# full_schema.net
KiCad netlist of a schematic drawn in EAGLE
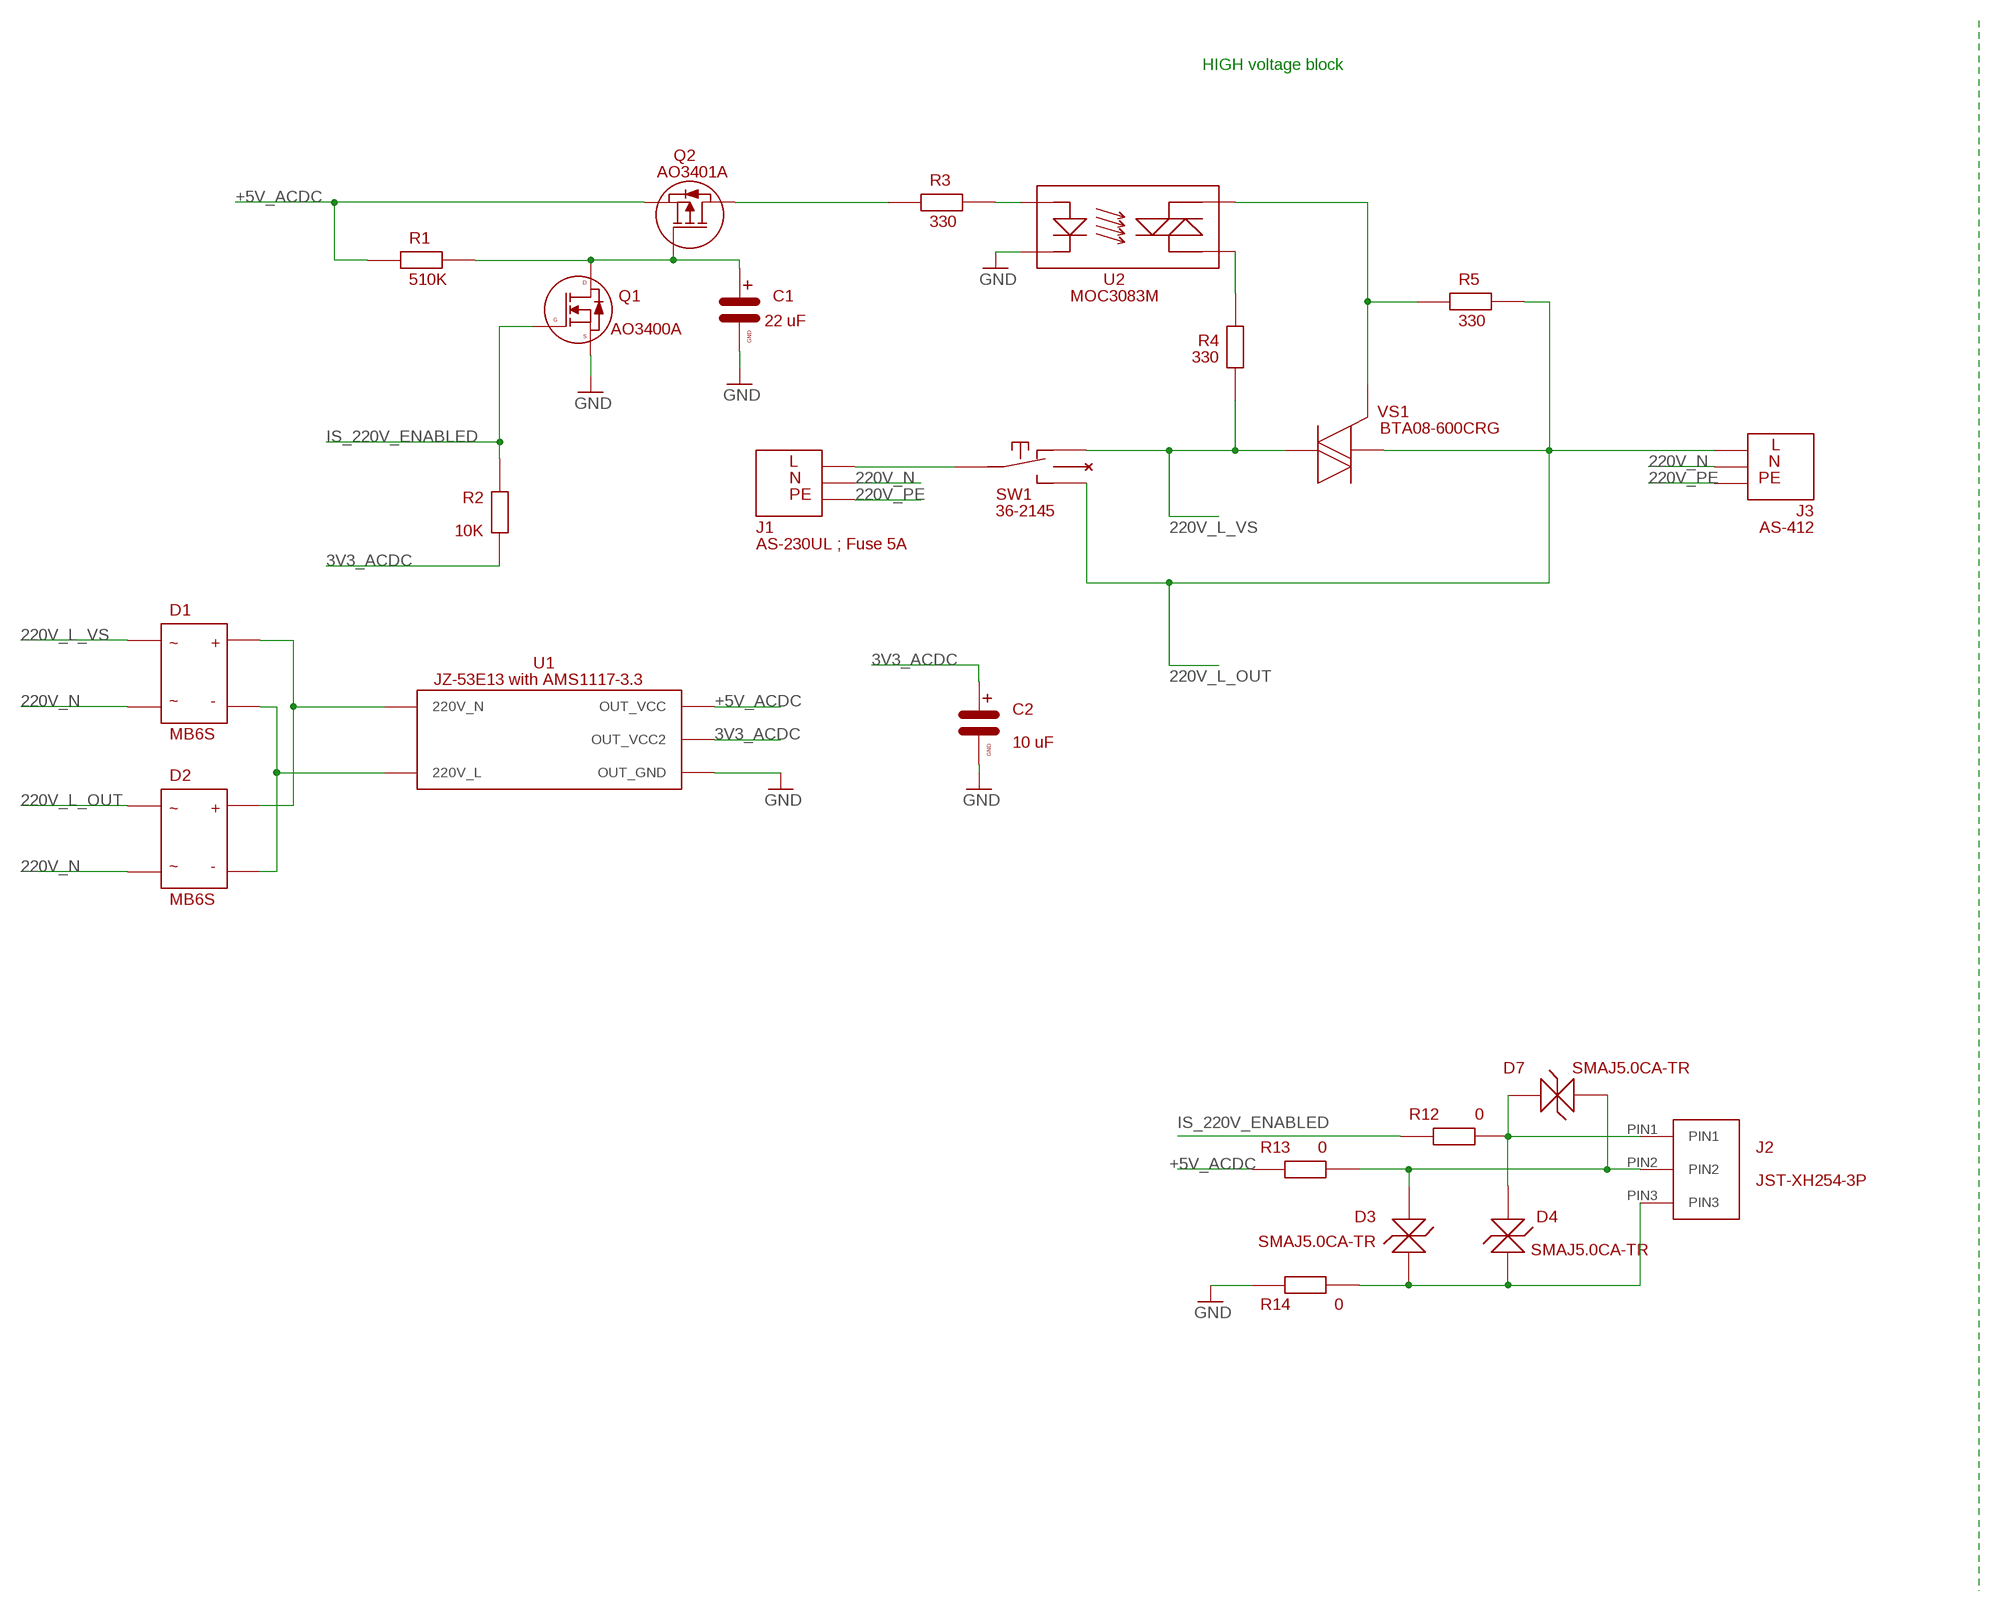
[diagram p0: schematic, sheet 1, part 1 of 2]
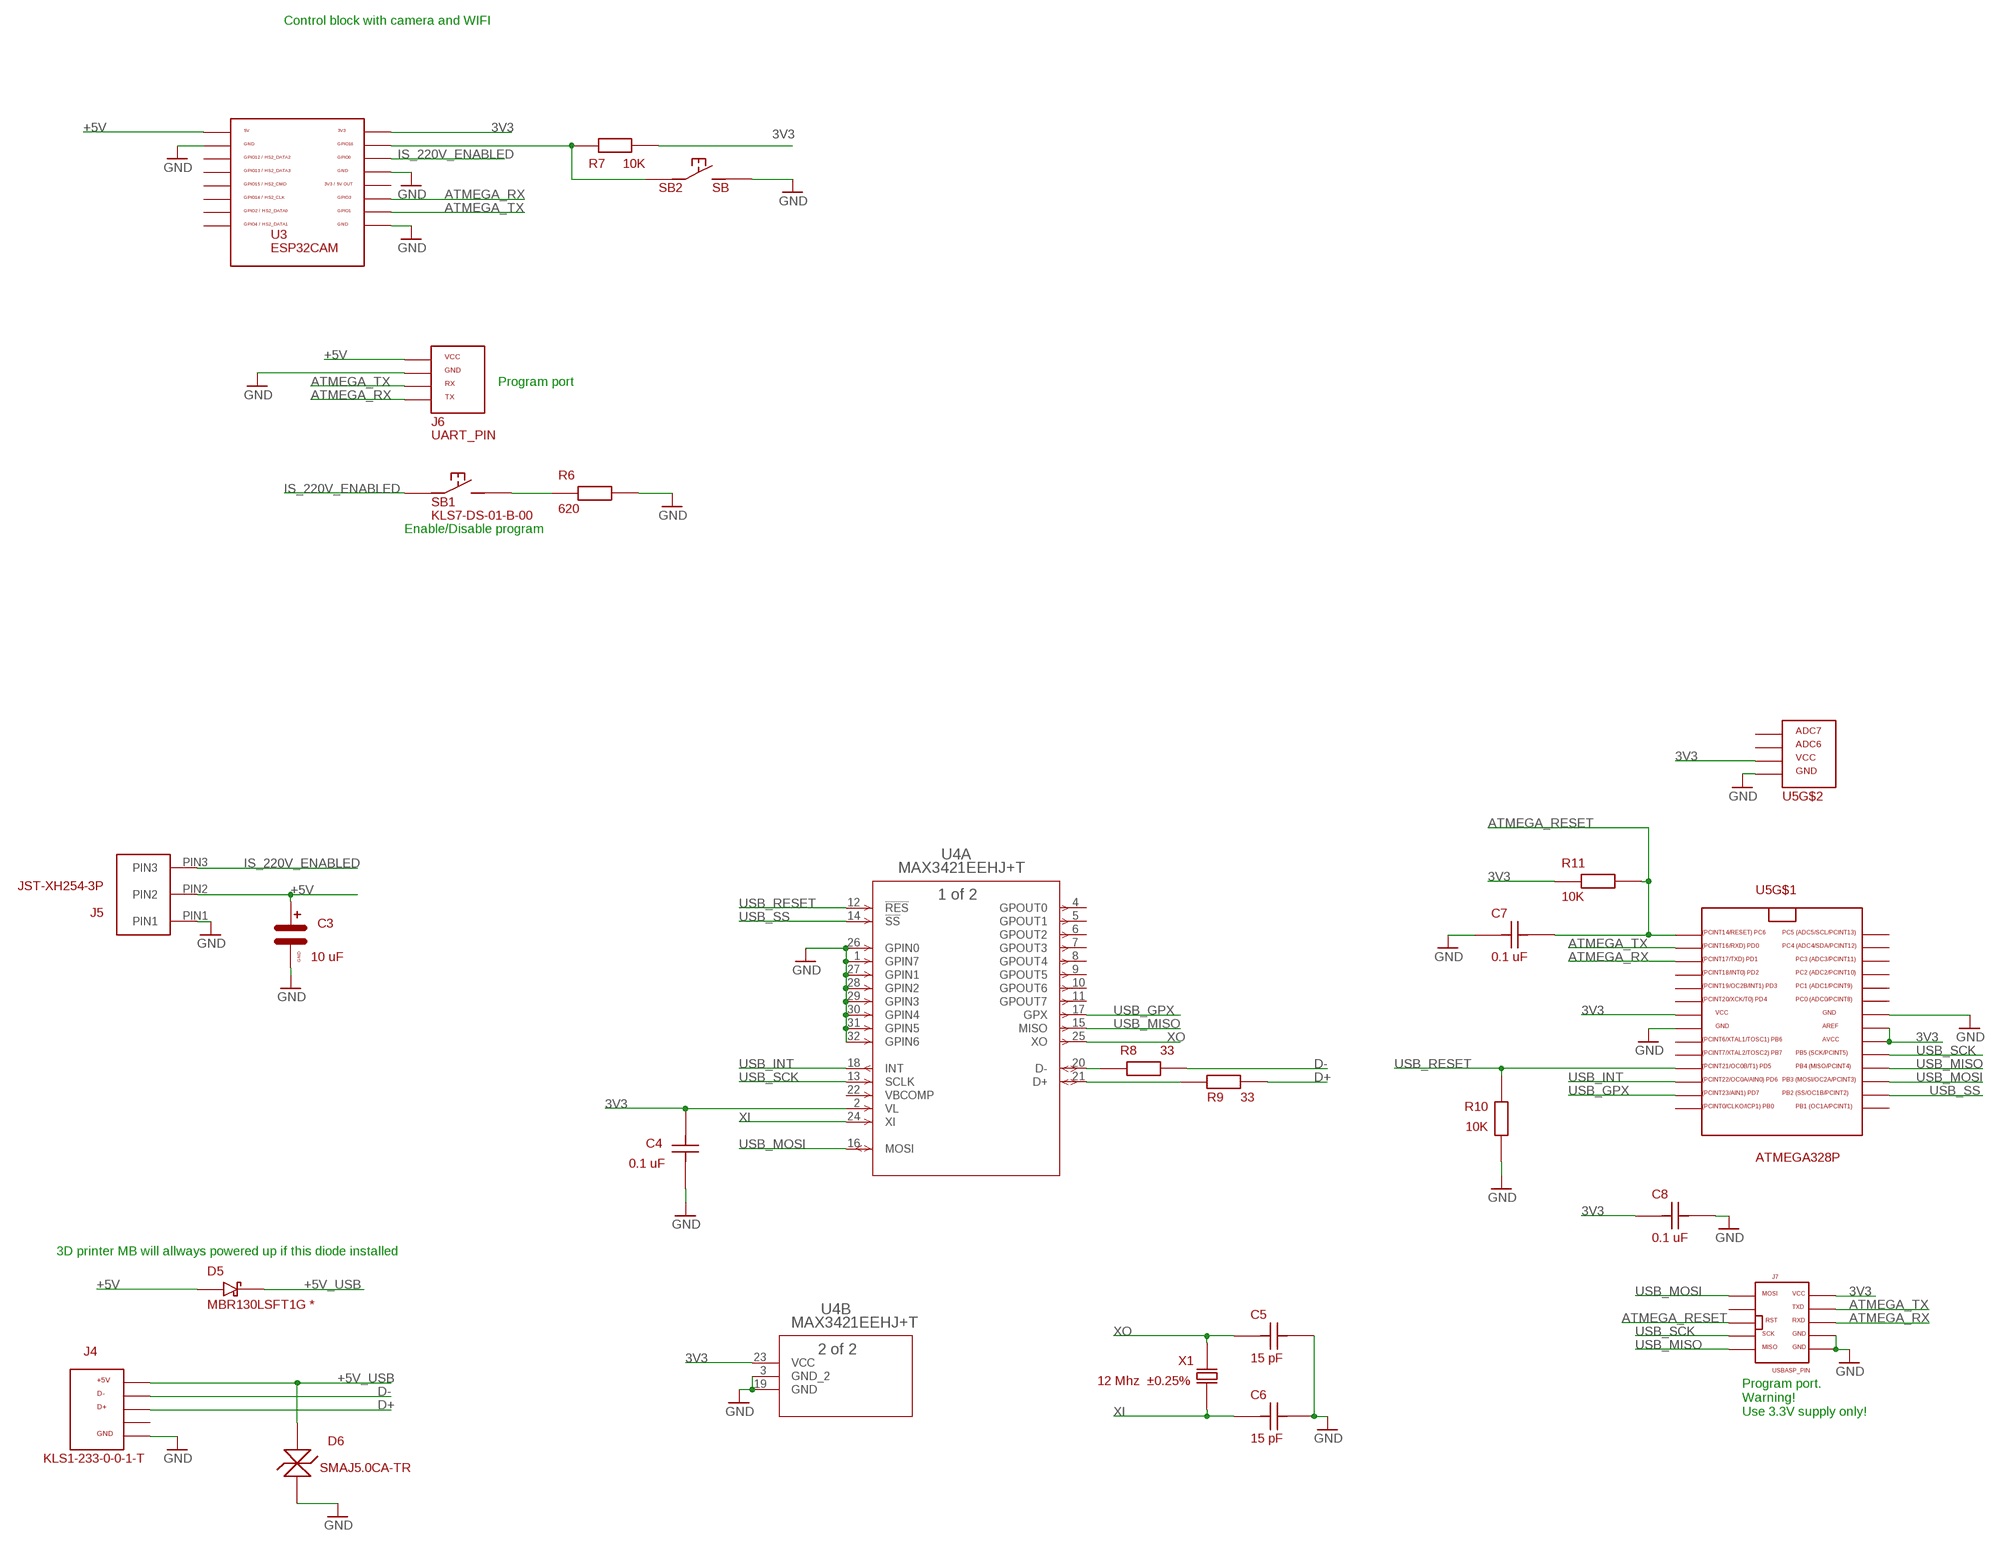
[diagram p1: schematic, sheet 1, part 2 of 2]

(export (version "E")
  (design (tool "Eeschema 10.0.6"))
  (components
    (comp (ref "C1")
      (value "22 uF")
      (footprint "eagle-import:C-MINI-5X7")
      (libsource (lib "eagle-import") (part "CMINI-5X7"))
    )
    (comp (ref "C2")
      (value "10 uF")
      (footprint "eagle-import:C-MINI-5X7")
      (libsource (lib "eagle-import") (part "CMINI-5X7"))
    )
    (comp (ref "C3")
      (value "10 uF")
      (footprint "eagle-import:C-MINI-5X7")
      (libsource (lib "eagle-import") (part "CMINI-5X7"))
    )
    (comp (ref "C4")
      (value "0.1 uF")
      (footprint "eagle-import:SMD_0805")
      (libsource (lib "eagle-import") (part "C-10805"))
    )
    (comp (ref "C5")
      (value "15 pF")
      (footprint "eagle-import:SMD_0805")
      (libsource (lib "eagle-import") (part "C-10805"))
    )
    (comp (ref "C6")
      (value "15 pF")
      (footprint "eagle-import:SMD_0805")
      (libsource (lib "eagle-import") (part "C-10805"))
    )
    (comp (ref "C7")
      (value "0.1 uF")
      (footprint "eagle-import:SMD_0805")
      (libsource (lib "eagle-import") (part "C-10805"))
    )
    (comp (ref "C8")
      (value "0.1 uF")
      (footprint "eagle-import:SMD_0805")
      (libsource (lib "eagle-import") (part "C-10805"))
    )
    (comp (ref "D1")
      (value "MB6S")
      (footprint "eagle-import:MBS")
      (libsource (lib "eagle-import") (part "DIODE_BRIDGEMBS"))
    )
    (comp (ref "D2")
      (value "MB6S")
      (footprint "eagle-import:MBS")
      (libsource (lib "eagle-import") (part "DIODE_BRIDGEMBS"))
    )
    (comp (ref "D3")
      (value "SMAJ5.0CA-TR")
      (footprint "eagle-import:DO-214AC")
      (libsource (lib "eagle-import") (part "D_ESDDO-214AC"))
    )
    (comp (ref "D4")
      (value "SMAJ5.0CA-TR")
      (footprint "eagle-import:DO-214AC")
      (libsource (lib "eagle-import") (part "D_ESDDO-214AC"))
    )
    (comp (ref "D5")
      (value "MBR130LSFT1G *")
      (footprint "eagle-import:D-SOD-123FL")
      (libsource (lib "eagle-import") (part "D_SCHOTTKYSOD-123FL"))
    )
    (comp (ref "D6")
      (value "SMAJ5.0CA-TR")
      (footprint "eagle-import:DO-214AC")
      (libsource (lib "eagle-import") (part "D_ESDDO-214AC"))
    )
    (comp (ref "D7")
      (value "SMAJ5.0CA-TR")
      (footprint "eagle-import:DO-214AC")
      (libsource (lib "eagle-import") (part "D_ESDDO-214AC"))
    )
    (comp (ref "J1")
      (value "AS-230UL ; Fuse 5A")
      (footprint "eagle-import:220V_CONNECTOR_EXTERNAL")
      (libsource (lib "eagle-import") (part "220V_CONNECTOREXT"))
    )
    (comp (ref "J2")
      (value "JST-XH254-3P")
      (footprint "eagle-import:JST-XH254-3P")
      (libsource (lib "eagle-import") (part "JST-XH254-3P"))
    )
    (comp (ref "J3")
      (value "AS-412")
      (footprint "eagle-import:220V_CONNECTOR_EXTERNAL")
      (libsource (lib "eagle-import") (part "220V_CONNECTOREXT"))
    )
    (comp (ref "J4")
      (value "KLS1-233-0-0-1-T")
      (footprint "eagle-import:MICROUSB")
      (libsource (lib "eagle-import") (part "J_MICROUSB"))
    )
    (comp (ref "J5")
      (value "JST-XH254-3P")
      (footprint "eagle-import:JST-XH254-3P")
      (libsource (lib "eagle-import") (part "JST-XH254-3P"))
    )
    (comp (ref "J6")
      (value "UART_PIN")
      (footprint "eagle-import:UART_PIN")
      (libsource (lib "eagle-import") (part "UART_PIN"))
    )
    (comp (ref "J7")
      (value "USBASP_PIN")
      (footprint "eagle-import:USBASP_PIN")
      (libsource (lib "eagle-import") (part "USBASP_PIN"))
    )
    (comp (ref "Q1")
      (value "AO3400A")
      (footprint "eagle-import:SOT-23-3")
      (libsource (lib "eagle-import") (part "MOSFET_NSOT-23-3"))
    )
    (comp (ref "Q2")
      (value "AO3401A")
      (footprint "eagle-import:SOT-23-3")
      (libsource (lib "eagle-import") (part "MOSFET_PSOT-23-3"))
    )
    (comp (ref "R1")
      (value "510K")
      (footprint "eagle-import:SMD_0805")
      (libsource (lib "eagle-import") (part "R0805"))
    )
    (comp (ref "R2")
      (value "10K")
      (footprint "eagle-import:SMD_0805")
      (libsource (lib "eagle-import") (part "R0805"))
    )
    (comp (ref "R3")
      (value "330")
      (footprint "eagle-import:SMD_0805")
      (libsource (lib "eagle-import") (part "R0805"))
    )
    (comp (ref "R4")
      (value "330")
      (footprint "eagle-import:SMD_0805")
      (libsource (lib "eagle-import") (part "R0805"))
    )
    (comp (ref "R5")
      (value "330")
      (footprint "eagle-import:SMD_0805")
      (libsource (lib "eagle-import") (part "R0805"))
    )
    (comp (ref "R6")
      (value "620")
      (footprint "eagle-import:SMD_0805")
      (libsource (lib "eagle-import") (part "R0805"))
    )
    (comp (ref "R7")
      (value "10K")
      (footprint "eagle-import:SMD_0805")
      (libsource (lib "eagle-import") (part "R0805"))
    )
    (comp (ref "R8")
      (value "33")
      (footprint "eagle-import:SMD_0805")
      (libsource (lib "eagle-import") (part "R0805"))
    )
    (comp (ref "R9")
      (value "33")
      (footprint "eagle-import:SMD_0805")
      (libsource (lib "eagle-import") (part "R0805"))
    )
    (comp (ref "R10")
      (value "10K")
      (footprint "eagle-import:SMD_0805")
      (libsource (lib "eagle-import") (part "R0805"))
    )
    (comp (ref "R11")
      (value "10K")
      (footprint "eagle-import:SMD_0805")
      (libsource (lib "eagle-import") (part "R0805"))
    )
    (comp (ref "R12")
      (value "0")
      (footprint "eagle-import:SMD_0805")
      (libsource (lib "eagle-import") (part "R0805"))
    )
    (comp (ref "R13")
      (value "0")
      (footprint "eagle-import:SMD_0805")
      (libsource (lib "eagle-import") (part "R0805"))
    )
    (comp (ref "R14")
      (value "0")
      (footprint "eagle-import:SMD_0805")
      (libsource (lib "eagle-import") (part "R0805"))
    )
    (comp (ref "SB1")
      (value "KLS7-DS-01-B-00")
      (footprint "eagle-import:SB-NC")
      (libsource (lib "eagle-import") (part "SB-NOSWITCH"))
    )
    (comp (ref "SB2")
      (value "SB")
      (footprint "eagle-import:SB-EXT")
      (libsource (lib "eagle-import") (part "SB-NOEXT_CONNECTOR"))
    )
    (comp (ref "SW1")
      (value "36-2145")
      (footprint "eagle-import:SWITCH_2")
      (libsource (lib "eagle-import") (part "SWITCH_2"))
    )
    (comp (ref "U1")
      (value "JZ-53E13 with AMS1117-3.3")
      (footprint "eagle-import:ACDC-30X20X18")
      (libsource (lib "eagle-import") (part "ACDC-2"))
    )
    (comp (ref "U2")
      (value "MOC3083M")
      (footprint "eagle-import:DIP6")
      (libsource (lib "eagle-import") (part "OPTRON"))
    )
    (comp (ref "U3")
      (value "ESP32CAM")
      (footprint "eagle-import:ESP32CAM")
      (libsource (lib "eagle-import") (part "ESP32CAM"))
    )
    (comp (ref "U4")
      (value "MAX3421EEHJ+T")
      (footprint "eagle-import:21-0110B_MXM-M")
      (fields
        (field (name "MANUFACTURER_PART_NUMBER") "MAX3421EEHJ+")
        (field (name "COPYRIGHT") "Copyright (C) 2022 Ultra Librarian. All rights reserved.")
      )
      (libsource (lib "eagle-import") (part "MAX3421EEHJ+21-0110B_MXM-M"))
    )
    (comp (ref "U5")
      (value "ATMEGA328P")
      (footprint "eagle-import:21-0110B_MXM-M")
      (libsource (lib "eagle-import") (part "ATMEGA328P-32PIN21-0110B_MXM-M"))
    )
    (comp (ref "VS1")
      (value "BTA08-600CRG")
      (footprint "eagle-import:TO-220AB")
      (libsource (lib "eagle-import") (part "TRIACTO-220AB"))
    )
    (comp (ref "X1")
      (value "12 Mhz ±0.25%")
      (footprint "eagle-import:HC-49U")
      (libsource (lib "eagle-import") (part "XHC-49U"))
    )
  )
  (nets
    (net (code "1") (name "/+5V") (class "Default")
      (node (ref "C3") (pin "PLUS") (pinfunction "PIN_PLUS_PLUS") (pintype "bidirectional"))
      (node (ref "D5") (pin "ANODE") (pinfunction "ANODE_ANODE") (pintype "bidirectional"))
      (node (ref "J5") (pin "PIN2") (pinfunction "PIN2_PIN2") (pintype "bidirectional"))
      (node (ref "J6") (pin "VCC") (pinfunction "VCC_VCC") (pintype "power_in"))
      (node (ref "U3") (pin "P9") (pinfunction "5V_P9") (pintype "power_in"))
    )
    (net (code "2") (name "/+5V_ACDC") (class "Default")
      (node (ref "Q2") (pin "P2") (pinfunction "S_P2") (pintype "bidirectional"))
      (node (ref "R1") (pin "P$1") (pinfunction "P$1_P$1") (pintype "bidirectional"))
      (node (ref "R13") (pin "P$1") (pinfunction "P$1_P$1") (pintype "bidirectional"))
      (node (ref "U1") (pin "OUT_VCC") (pinfunction "OUT_VCC_OUT_VCC") (pintype "power_in"))
    )
    (net (code "3") (name "/+5V_USB") (class "Default")
      (node (ref "D5") (pin "CATHODE") (pinfunction "CATHODE_CATHODE") (pintype "bidirectional"))
      (node (ref "D6") (pin "P$2") (pinfunction "P2_P$2") (pintype "bidirectional"))
      (node (ref "J4") (pin "+5V") (pinfunction "+5V_+5V") (pintype "bidirectional"))
    )
    (net (code "4") (name "/3V3") (class "Default")
      (node (ref "C4") (pin "P$2") (pinfunction "P$2_P$2") (pintype "bidirectional"))
      (node (ref "C8") (pin "P$1") (pinfunction "P$1_P$1") (pintype "bidirectional"))
      (node (ref "J7") (pin "VCC") (pinfunction "VCC_VCC") (pintype "power_in"))
      (node (ref "R11") (pin "P$1") (pinfunction "P$1_P$1") (pintype "bidirectional"))
      (node (ref "R7") (pin "P$1") (pinfunction "P$1_P$1") (pintype "bidirectional"))
      (node (ref "U3") (pin "P8") (pinfunction "3V3_P8") (pintype "power_in"))
      (node (ref "U4") (pin "2") (pinfunction "VL_2") (pintype "input"))
      (node (ref "U4") (pin "23") (pinfunction "VCC_23") (pintype "power_in"))
      (node (ref "U5") (pin "18") (pinfunction "AVCC_18") (pintype "power_in"))
      (node (ref "U5") (pin "20") (pinfunction "AREF_20") (pintype "bidirectional"))
      (node (ref "U5") (pin "4") (pinfunction "VCC_4") (pintype "power_in"))
      (node (ref "U5") (pin "6") (pinfunction "VCC_6") (pintype "bidirectional"))
    )
    (net (code "5") (name "/3V3_ACDC") (class "Default")
      (node (ref "C2") (pin "PLUS") (pinfunction "PIN_PLUS_PLUS") (pintype "bidirectional"))
      (node (ref "R2") (pin "P$1") (pinfunction "P$1_P$1") (pintype "bidirectional"))
      (node (ref "U1") (pin "OUT_VCC2") (pinfunction "OUT_VCC2_OUT_VCC2") (pintype "power_in"))
    )
    (net (code "6") (name "/220V_L_OUT") (class "Default")
      (node (ref "D2") (pin "P1") (pinfunction "AC1_P1") (pintype "power_in"))
      (node (ref "J3") (pin "L") (pinfunction "L_L") (pintype "power_in"))
      (node (ref "R5") (pin "P$2") (pinfunction "P$2_P$2") (pintype "bidirectional"))
      (node (ref "SW1") (pin "OUT2") (pinfunction "OUT2_OUT2") (pintype "bidirectional"))
      (node (ref "VS1") (pin "P1") (pinfunction "A1_P1") (pintype "bidirectional"))
    )
    (net (code "7") (name "/220V_L_VS") (class "Default")
      (node (ref "D1") (pin "P1") (pinfunction "AC1_P1") (pintype "power_in"))
      (node (ref "R4") (pin "P$1") (pinfunction "P$1_P$1") (pintype "bidirectional"))
      (node (ref "SW1") (pin "OUT1") (pinfunction "OUT1_OUT1") (pintype "bidirectional"))
      (node (ref "VS1") (pin "P2") (pinfunction "A2_P2") (pintype "bidirectional"))
    )
    (net (code "8") (name "/220V_N") (class "Default")
      (node (ref "D1") (pin "P2") (pinfunction "AC2_P2") (pintype "power_in"))
      (node (ref "D2") (pin "P2") (pinfunction "AC2_P2") (pintype "power_in"))
      (node (ref "J1") (pin "N") (pinfunction "N_N") (pintype "power_in"))
      (node (ref "J3") (pin "N") (pinfunction "N_N") (pintype "power_in"))
    )
    (net (code "9") (name "/220V_PE") (class "Default")
      (node (ref "J1") (pin "PE\\") (pinfunction "PE_PE\\") (pintype "power_in"))
      (node (ref "J3") (pin "PE\\") (pinfunction "PE_PE\\") (pintype "power_in"))
    )
    (net (code "10") (name "/ATMEGA_RESET") (class "Default")
      (node (ref "C7") (pin "P$2") (pinfunction "P$2_P$2") (pintype "bidirectional"))
      (node (ref "J7") (pin "RST") (pinfunction "RESET_RST") (pintype "bidirectional"))
      (node (ref "R11") (pin "P$2") (pinfunction "P$2_P$2") (pintype "bidirectional"))
      (node (ref "U5") (pin "29") (pinfunction "PC6_29") (pintype "bidirectional"))
    )
    (net (code "11") (name "/ATMEGA_RX") (class "Default")
      (node (ref "J6") (pin "TX") (pinfunction "TX_TX") (pintype "bidirectional"))
      (node (ref "J7") (pin "RXD") (pinfunction "RXD_RXD") (pintype "bidirectional"))
      (node (ref "U3") (pin "P3") (pinfunction "GPIO3_P3") (pintype "bidirectional"))
      (node (ref "U5") (pin "31") (pinfunction "PD1_31") (pintype "bidirectional"))
    )
    (net (code "12") (name "/ATMEGA_TX") (class "Default")
      (node (ref "J6") (pin "RX") (pinfunction "RX_RX") (pintype "bidirectional"))
      (node (ref "J7") (pin "TXD") (pinfunction "TXD_TXD") (pintype "bidirectional"))
      (node (ref "U3") (pin "P2") (pinfunction "GPIO1_P2") (pintype "bidirectional"))
      (node (ref "U5") (pin "30") (pinfunction "PD0_30") (pintype "bidirectional"))
    )
    (net (code "13") (name "/D+") (class "Default")
      (node (ref "J4") (pin "D+") (pinfunction "D+_D+") (pintype "bidirectional"))
      (node (ref "R9") (pin "P$2") (pinfunction "P$2_P$2") (pintype "bidirectional"))
    )
    (net (code "14") (name "/D-") (class "Default")
      (node (ref "J4") (pin "D-") (pinfunction "D-_D-") (pintype "bidirectional"))
      (node (ref "R8") (pin "P$2") (pinfunction "P$2_P$2") (pintype "bidirectional"))
    )
    (net (code "15") (name "/IS_220V_ENABLED") (class "Default")
      (node (ref "J5") (pin "PIN3") (pinfunction "PIN3_PIN3") (pintype "bidirectional"))
      (node (ref "Q1") (pin "P1") (pinfunction "G_P1") (pintype "bidirectional"))
      (node (ref "R12") (pin "P$1") (pinfunction "P$1_P$1") (pintype "bidirectional"))
      (node (ref "R2") (pin "P$2") (pinfunction "P$2_P$2") (pintype "bidirectional"))
      (node (ref "SB1") (pin "P$1") (pinfunction "P$1_P$1") (pintype "bidirectional"))
      (node (ref "U3") (pin "P6") (pinfunction "GPIO0_P6") (pintype "bidirectional"))
    )
    (net (code "16") (name "/USB_GPX") (class "Default")
      (node (ref "U4") (pin "17") (pinfunction "GPX_17") (pintype "output"))
      (node (ref "U5") (pin "11") (pinfunction "PD7_11") (pintype "bidirectional"))
    )
    (net (code "17") (name "/USB_INT") (class "Default")
      (node (ref "U4") (pin "18") (pinfunction "INT_18") (pintype "output"))
      (node (ref "U5") (pin "10") (pinfunction "PD6_10") (pintype "bidirectional"))
    )
    (net (code "18") (name "/USB_MISO") (class "Default")
      (node (ref "J7") (pin "MISO") (pinfunction "MISO_MISO") (pintype "bidirectional"))
      (node (ref "U4") (pin "15") (pinfunction "MISO_15") (pintype "output"))
      (node (ref "U5") (pin "16") (pinfunction "PB4_16") (pintype "bidirectional"))
    )
    (net (code "19") (name "/USB_MOSI") (class "Default")
      (node (ref "J7") (pin "MOSI") (pinfunction "MOSI_MOSI") (pintype "bidirectional"))
      (node (ref "U4") (pin "16") (pinfunction "MOSI_16") (pintype "bidirectional"))
      (node (ref "U5") (pin "15") (pinfunction "PB3_15") (pintype "bidirectional"))
    )
    (net (code "20") (name "/USB_RESET") (class "Default")
      (node (ref "R10") (pin "P$2") (pinfunction "P$2_P$2") (pintype "bidirectional"))
      (node (ref "U4") (pin "12") (pinfunction "~{RES}_12") (pintype "input"))
      (node (ref "U5") (pin "9") (pinfunction "PD5_9") (pintype "bidirectional"))
    )
    (net (code "21") (name "/USB_SCK") (class "Default")
      (node (ref "J7") (pin "SCK") (pinfunction "SCK_SCK") (pintype "bidirectional"))
      (node (ref "U4") (pin "13") (pinfunction "SCLK_13") (pintype "input"))
      (node (ref "U5") (pin "17") (pinfunction "PB5_17") (pintype "bidirectional"))
    )
    (net (code "22") (name "/USB_SS") (class "Default")
      (node (ref "U4") (pin "14") (pinfunction "~{SS}_14") (pintype "input"))
      (node (ref "U5") (pin "14") (pinfunction "PB2_14") (pintype "bidirectional"))
    )
    (net (code "23") (name "/XI") (class "Default")
      (node (ref "C6") (pin "P$1") (pinfunction "P$1_P$1") (pintype "bidirectional"))
      (node (ref "U4") (pin "24") (pinfunction "XI_24") (pintype "input"))
      (node (ref "X1") (pin "P$1") (pinfunction "P$1_P$1") (pintype "bidirectional"))
    )
    (net (code "24") (name "/XO") (class "Default")
      (node (ref "C5") (pin "P$1") (pinfunction "P$1_P$1") (pintype "bidirectional"))
      (node (ref "U4") (pin "25") (pinfunction "XO_25") (pintype "output"))
      (node (ref "X1") (pin "P$2") (pinfunction "P$2_P$2") (pintype "bidirectional"))
    )
    (net (code "25") (name "GND") (class "Default")
      (node (ref "C1") (pin "MINUS") (pinfunction "PIN_GND_MINUS") (pintype "bidirectional"))
      (node (ref "C2") (pin "MINUS") (pinfunction "PIN_GND_MINUS") (pintype "bidirectional"))
      (node (ref "C3") (pin "MINUS") (pinfunction "PIN_GND_MINUS") (pintype "bidirectional"))
      (node (ref "C4") (pin "P$1") (pinfunction "P$1_P$1") (pintype "bidirectional"))
      (node (ref "C5") (pin "P$2") (pinfunction "P$2_P$2") (pintype "bidirectional"))
      (node (ref "C6") (pin "P$2") (pinfunction "P$2_P$2") (pintype "bidirectional"))
      (node (ref "C7") (pin "P$1") (pinfunction "P$1_P$1") (pintype "bidirectional"))
      (node (ref "C8") (pin "P$2") (pinfunction "P$2_P$2") (pintype "bidirectional"))
      (node (ref "D1") (pin "P4") (pinfunction "GND_P4") (pintype "power_in"))
      (node (ref "D2") (pin "P4") (pinfunction "GND_P4") (pintype "power_in"))
      (node (ref "D6") (pin "P$1") (pinfunction "P1_P$1") (pintype "bidirectional"))
      (node (ref "J4") (pin "GND") (pinfunction "GND_GND") (pintype "bidirectional"))
      (node (ref "J5") (pin "PIN1") (pinfunction "PIN1_PIN1") (pintype "bidirectional"))
      (node (ref "J6") (pin "GND") (pinfunction "GND_GND") (pintype "power_in"))
      (node (ref "J7") (pin "GND") (pinfunction "GND_GND") (pintype "power_in"))
      (node (ref "J7") (pin "GND1") (pinfunction "GND1_GND1") (pintype "power_in"))
      (node (ref "Q1") (pin "P2") (pinfunction "S_P2") (pintype "bidirectional"))
      (node (ref "R10") (pin "P$1") (pinfunction "P$1_P$1") (pintype "bidirectional"))
      (node (ref "R14") (pin "P$1") (pinfunction "P$1_P$1") (pintype "bidirectional"))
      (node (ref "R6") (pin "P$2") (pinfunction "P$2_P$2") (pintype "bidirectional"))
      (node (ref "SB2") (pin "P$2") (pinfunction "P$2_P$2") (pintype "bidirectional"))
      (node (ref "U1") (pin "220V_L") (pinfunction "220V_L_220V_L") (pintype "power_in"))
      (node (ref "U1") (pin "OUT_GND") (pinfunction "OUT_GND_OUT_GND") (pintype "power_in"))
      (node (ref "U2") (pin "P2") (pinfunction "IN_CATHODE_P2") (pintype "bidirectional"))
      (node (ref "U3") (pin "P1") (pinfunction "GND2_P1") (pintype "power_in"))
      (node (ref "U3") (pin "P10") (pinfunction "GND_P10") (pintype "power_in"))
      (node (ref "U3") (pin "P5") (pinfunction "GND1_P5") (pintype "power_in"))
      (node (ref "U4") (pin "1") (pinfunction "GPIN7_1") (pintype "input"))
      (node (ref "U4") (pin "19") (pinfunction "GND_19") (pintype "power_in"))
      (node (ref "U4") (pin "26") (pinfunction "GPIN0_26") (pintype "input"))
      (node (ref "U4") (pin "27") (pinfunction "GPIN1_27") (pintype "input"))
      (node (ref "U4") (pin "28") (pinfunction "GPIN2_28") (pintype "input"))
      (node (ref "U4") (pin "29") (pinfunction "GPIN3_29") (pintype "input"))
      (node (ref "U4") (pin "3") (pinfunction "GND_2_3") (pintype "power_in"))
      (node (ref "U4") (pin "30") (pinfunction "GPIN4_30") (pintype "input"))
      (node (ref "U4") (pin "31") (pinfunction "GPIN5_31") (pintype "input"))
      (node (ref "U4") (pin "32") (pinfunction "GPIN6_32") (pintype "input"))
      (node (ref "U5") (pin "21") (pinfunction "GND1_21") (pintype "power_in"))
      (node (ref "U5") (pin "3") (pinfunction "GND_3") (pintype "power_in"))
      (node (ref "U5") (pin "5") (pinfunction "GND_5") (pintype "bidirectional"))
    )
    (net (code "26") (name "Net-(C1-PIN_PLUS)") (class "Default")
      (node (ref "C1") (pin "PLUS") (pinfunction "PIN_PLUS_PLUS") (pintype "bidirectional"))
      (node (ref "Q1") (pin "P3") (pinfunction "D_P3") (pintype "bidirectional"))
      (node (ref "Q2") (pin "P1") (pinfunction "G_P1") (pintype "bidirectional"))
      (node (ref "R1") (pin "P$2") (pinfunction "P$2_P$2") (pintype "bidirectional"))
    )
    (net (code "27") (name "Net-(D1-VCC)") (class "Default")
      (node (ref "D1") (pin "P3") (pinfunction "VCC_P3") (pintype "power_in"))
      (node (ref "D2") (pin "P3") (pinfunction "VCC_P3") (pintype "power_in"))
      (node (ref "U1") (pin "220V_N") (pinfunction "220V_N_220V_N") (pintype "power_in"))
    )
    (net (code "28") (name "Net-(D3-P1)") (class "Default")
      (node (ref "D3") (pin "P$1") (pinfunction "P1_P$1") (pintype "bidirectional"))
      (node (ref "D4") (pin "P$1") (pinfunction "P1_P$1") (pintype "bidirectional"))
      (node (ref "J2") (pin "PIN3") (pinfunction "PIN3_PIN3") (pintype "bidirectional"))
      (node (ref "R14") (pin "P$2") (pinfunction "P$2_P$2") (pintype "bidirectional"))
    )
    (net (code "29") (name "Net-(D3-P2)") (class "Default")
      (node (ref "D3") (pin "P$2") (pinfunction "P2_P$2") (pintype "bidirectional"))
      (node (ref "D7") (pin "P$1") (pinfunction "P1_P$1") (pintype "bidirectional"))
      (node (ref "J2") (pin "PIN2") (pinfunction "PIN2_PIN2") (pintype "bidirectional"))
      (node (ref "R13") (pin "P$2") (pinfunction "P$2_P$2") (pintype "bidirectional"))
    )
    (net (code "30") (name "Net-(D4-P2)") (class "Default")
      (node (ref "D4") (pin "P$2") (pinfunction "P2_P$2") (pintype "bidirectional"))
      (node (ref "D7") (pin "P$2") (pinfunction "P2_P$2") (pintype "bidirectional"))
      (node (ref "J2") (pin "PIN1") (pinfunction "PIN1_PIN1") (pintype "bidirectional"))
      (node (ref "R12") (pin "P$2") (pinfunction "P$2_P$2") (pintype "bidirectional"))
    )
    (net (code "31") (name "Net-(J1-PadL)") (class "Default")
      (node (ref "J1") (pin "L") (pinfunction "L_L") (pintype "power_in"))
      (node (ref "SW1") (pin "IN") (pinfunction "IN_IN") (pintype "bidirectional"))
    )
    (net (code "32") (name "Net-(Q2-D)") (class "Default")
      (node (ref "Q2") (pin "P3") (pinfunction "D_P3") (pintype "bidirectional"))
      (node (ref "R3") (pin "P$1") (pinfunction "P$1_P$1") (pintype "bidirectional"))
    )
    (net (code "33") (name "Net-(R6-PadP$1)") (class "Default")
      (node (ref "R6") (pin "P$1") (pinfunction "P$1_P$1") (pintype "bidirectional"))
      (node (ref "SB1") (pin "P$2") (pinfunction "P$2_P$2") (pintype "bidirectional"))
    )
    (net (code "34") (name "Net-(U2-IN_ANODE)") (class "Default")
      (node (ref "R3") (pin "P$2") (pinfunction "P$2_P$2") (pintype "bidirectional"))
      (node (ref "U2") (pin "P1") (pinfunction "IN_ANODE_P1") (pintype "bidirectional"))
    )
    (net (code "35") (name "Net-(U2-OUT_1)") (class "Default")
      (node (ref "R5") (pin "P$1") (pinfunction "P$1_P$1") (pintype "bidirectional"))
      (node (ref "U2") (pin "P4") (pinfunction "OUT_1_P4") (pintype "bidirectional"))
      (node (ref "VS1") (pin "P3") (pinfunction "GATE_P3") (pintype "bidirectional"))
    )
    (net (code "36") (name "Net-(U2-OUT_2)") (class "Default")
      (node (ref "R4") (pin "P$2") (pinfunction "P$2_P$2") (pintype "bidirectional"))
      (node (ref "U2") (pin "P6") (pinfunction "OUT_2_P6") (pintype "bidirectional"))
    )
    (net (code "37") (name "Net-(U3-GPIO16)") (class "Default")
      (node (ref "R7") (pin "P$2") (pinfunction "P$2_P$2") (pintype "bidirectional"))
      (node (ref "SB2") (pin "P$1") (pinfunction "P$1_P$1") (pintype "bidirectional"))
      (node (ref "U3") (pin "P7") (pinfunction "GPIO16_P7") (pintype "bidirectional"))
    )
    (net (code "38") (name "Net-(U4A-D+)") (class "Default")
      (node (ref "R9") (pin "P$1") (pinfunction "P$1_P$1") (pintype "bidirectional"))
      (node (ref "U4") (pin "21") (pinfunction "D+_21") (pintype "bidirectional"))
    )
    (net (code "39") (name "Net-(U4A-D-)") (class "Default")
      (node (ref "R8") (pin "P$1") (pinfunction "P$1_P$1") (pintype "bidirectional"))
      (node (ref "U4") (pin "20") (pinfunction "D-_20") (pintype "bidirectional"))
    )
    (net (code "40") (name "unconnected-(J4-PadNC)") (class "Default")
      (node (ref "J4") (pin "NC") (pinfunction "NC_NC") (pintype "no_connect"))
    )
    (net (code "41") (name "unconnected-(J7-PadNC1)") (class "Default")
      (node (ref "J7") (pin "NC1") (pinfunction "NC1_NC1") (pintype "no_connect"))
    )
    (net (code "42") (name "unconnected-(U3-3V3_5V_OUT-PadP4)") (class "Default")
      (node (ref "U3") (pin "P4") (pinfunction "3V3_5V_OUT_P4") (pintype "bidirectional"))
    )
    (net (code "43") (name "unconnected-(U3-GPIO2-PadP15)") (class "Default")
      (node (ref "U3") (pin "P15") (pinfunction "GPIO2_P15") (pintype "bidirectional"))
    )
    (net (code "44") (name "unconnected-(U3-GPIO4-PadP16)") (class "Default")
      (node (ref "U3") (pin "P16") (pinfunction "GPIO4_P16") (pintype "bidirectional"))
    )
    (net (code "45") (name "unconnected-(U3-GPIO12-PadP11)") (class "Default")
      (node (ref "U3") (pin "P11") (pinfunction "GPIO12_P11") (pintype "bidirectional"))
    )
    (net (code "46") (name "unconnected-(U3-GPIO13-PadP12)") (class "Default")
      (node (ref "U3") (pin "P12") (pinfunction "GPIO13_P12") (pintype "bidirectional"))
    )
    (net (code "47") (name "unconnected-(U3-GPIO14-PadP14)") (class "Default")
      (node (ref "U3") (pin "P14") (pinfunction "GPIO14_P14") (pintype "bidirectional"))
    )
    (net (code "48") (name "unconnected-(U3-GPIO15-PadP13)") (class "Default")
      (node (ref "U3") (pin "P13") (pinfunction "GPIO15_P13") (pintype "bidirectional"))
    )
    (net (code "49") (name "unconnected-(U4A-GPOUT0-Pad4)") (class "Default")
      (node (ref "U4") (pin "4") (pinfunction "GPOUT0_4") (pintype "output"))
    )
    (net (code "50") (name "unconnected-(U4A-GPOUT1-Pad5)") (class "Default")
      (node (ref "U4") (pin "5") (pinfunction "GPOUT1_5") (pintype "output"))
    )
    (net (code "51") (name "unconnected-(U4A-GPOUT2-Pad6)") (class "Default")
      (node (ref "U4") (pin "6") (pinfunction "GPOUT2_6") (pintype "output"))
    )
    (net (code "52") (name "unconnected-(U4A-GPOUT3-Pad7)") (class "Default")
      (node (ref "U4") (pin "7") (pinfunction "GPOUT3_7") (pintype "output"))
    )
    (net (code "53") (name "unconnected-(U4A-GPOUT4-Pad8)") (class "Default")
      (node (ref "U4") (pin "8") (pinfunction "GPOUT4_8") (pintype "output"))
    )
    (net (code "54") (name "unconnected-(U4A-GPOUT5-Pad9)") (class "Default")
      (node (ref "U4") (pin "9") (pinfunction "GPOUT5_9") (pintype "output"))
    )
    (net (code "55") (name "unconnected-(U4A-GPOUT6-Pad10)") (class "Default")
      (node (ref "U4") (pin "10") (pinfunction "GPOUT6_10") (pintype "output"))
    )
    (net (code "56") (name "unconnected-(U4A-GPOUT7-Pad11)") (class "Default")
      (node (ref "U4") (pin "11") (pinfunction "GPOUT7_11") (pintype "output"))
    )
    (net (code "57") (name "unconnected-(U4A-VBCOMP-Pad22)") (class "Default")
      (node (ref "U4") (pin "22") (pinfunction "VBCOMP_22") (pintype "input"))
    )
    (net (code "58") (name "unconnected-(U5A-PB0-Pad12)") (class "Default")
      (node (ref "U5") (pin "12") (pinfunction "PB0_12") (pintype "bidirectional"))
    )
    (net (code "59") (name "unconnected-(U5A-PB1-Pad13)") (class "Default")
      (node (ref "U5") (pin "13") (pinfunction "PB1_13") (pintype "bidirectional"))
    )
    (net (code "60") (name "unconnected-(U5A-PB6-Pad7)") (class "Default")
      (node (ref "U5") (pin "7") (pinfunction "PB6_7") (pintype "bidirectional"))
    )
    (net (code "61") (name "unconnected-(U5A-PB7-Pad8)") (class "Default")
      (node (ref "U5") (pin "8") (pinfunction "PB7_8") (pintype "bidirectional"))
    )
    (net (code "62") (name "unconnected-(U5A-PC0-Pad23)") (class "Default")
      (node (ref "U5") (pin "23") (pinfunction "PC0_23") (pintype "bidirectional"))
    )
    (net (code "63") (name "unconnected-(U5A-PC1-Pad24)") (class "Default")
      (node (ref "U5") (pin "24") (pinfunction "PC1_24") (pintype "bidirectional"))
    )
    (net (code "64") (name "unconnected-(U5A-PC2-Pad25)") (class "Default")
      (node (ref "U5") (pin "25") (pinfunction "PC2_25") (pintype "bidirectional"))
    )
    (net (code "65") (name "unconnected-(U5A-PC3-Pad26)") (class "Default")
      (node (ref "U5") (pin "26") (pinfunction "PC3_26") (pintype "bidirectional"))
    )
    (net (code "66") (name "unconnected-(U5A-PC4-Pad27)") (class "Default")
      (node (ref "U5") (pin "27") (pinfunction "PC4_27") (pintype "bidirectional"))
    )
    (net (code "67") (name "unconnected-(U5A-PC5-Pad28)") (class "Default")
      (node (ref "U5") (pin "28") (pinfunction "PC5_28") (pintype "bidirectional"))
    )
    (net (code "68") (name "unconnected-(U5A-PD2-Pad32)") (class "Default")
      (node (ref "U5") (pin "32") (pinfunction "PD2_32") (pintype "bidirectional"))
    )
    (net (code "69") (name "unconnected-(U5A-PD3-Pad1)") (class "Default")
      (node (ref "U5") (pin "1") (pinfunction "PD3_1") (pintype "bidirectional"))
    )
    (net (code "70") (name "unconnected-(U5A-PD4-Pad2)") (class "Default")
      (node (ref "U5") (pin "2") (pinfunction "PD4_2") (pintype "bidirectional"))
    )
    (net (code "71") (name "unconnected-(U5B-ADC6-Pad19)") (class "Default")
      (node (ref "U5") (pin "19") (pinfunction "ADC6_19") (pintype "bidirectional"))
    )
    (net (code "72") (name "unconnected-(U5B-ADC7-Pad22)") (class "Default")
      (node (ref "U5") (pin "22") (pinfunction "ADC7_22") (pintype "bidirectional"))
    )
  )
)
